# mega2560_EasyEDA_file.net
KiCad netlist of a schematic drawn in EasyEDA
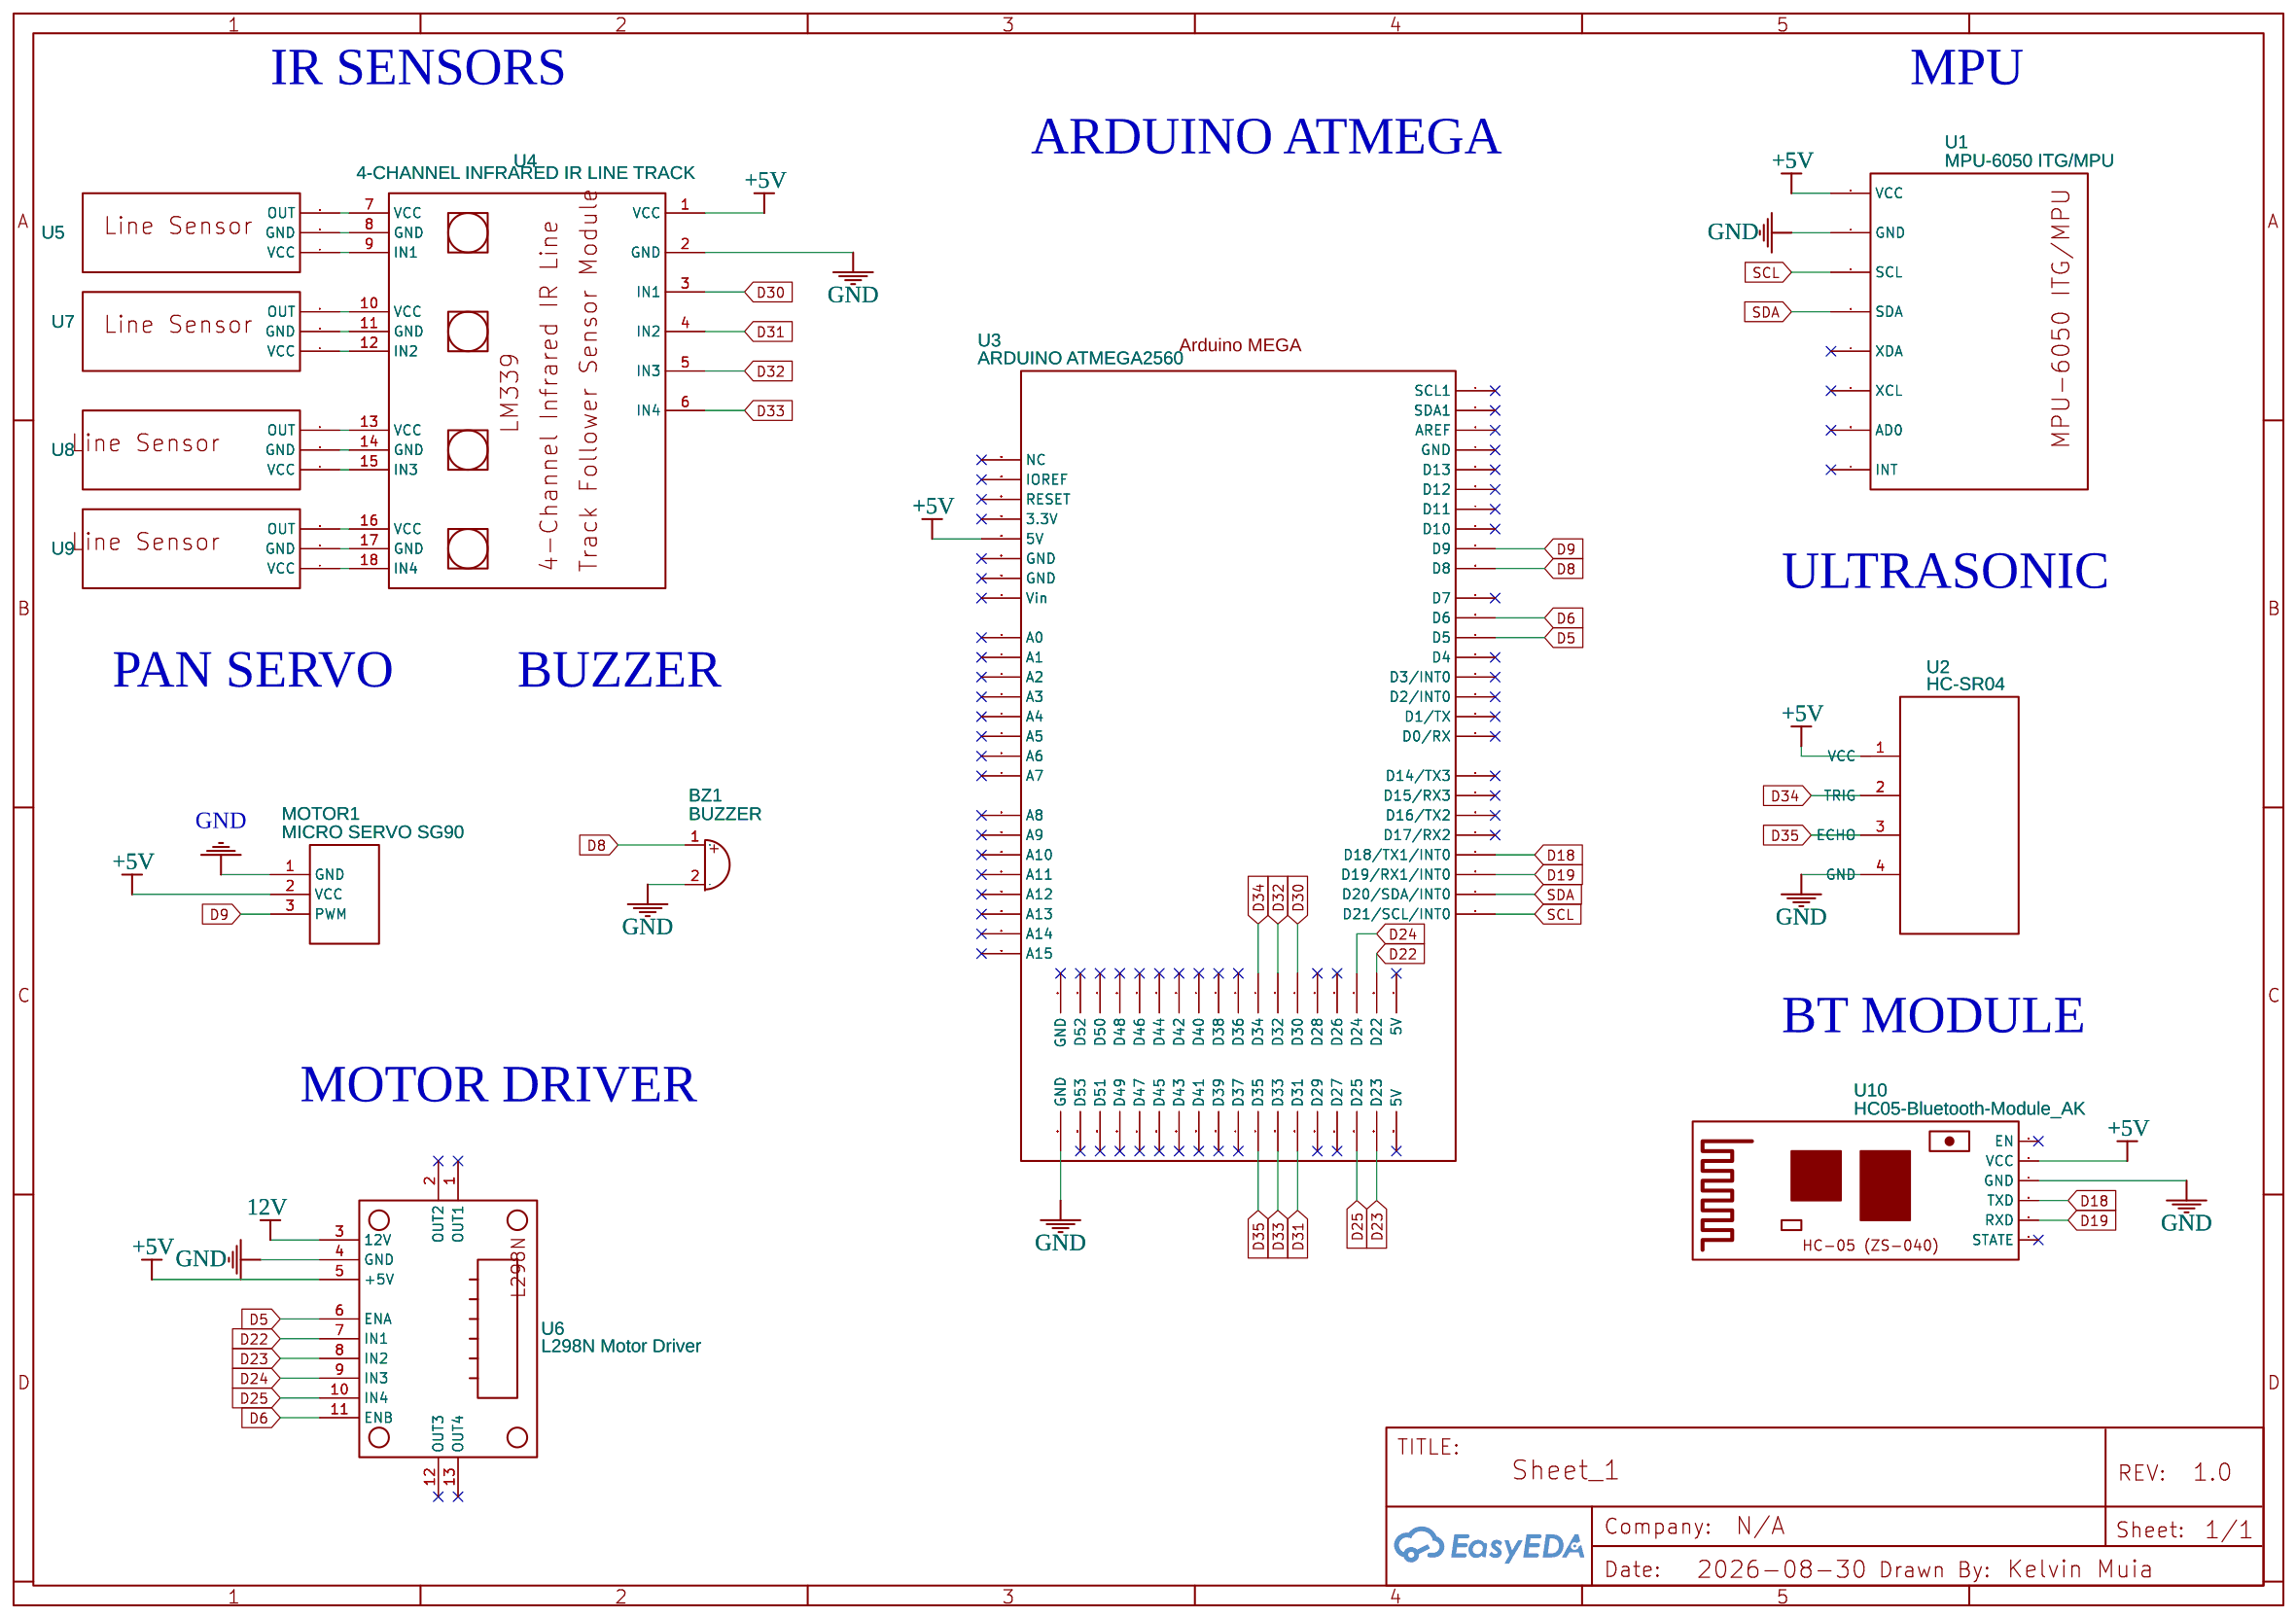
[diagram p0: schematic sheet]

(export (version "E")
  (design (tool "Eeschema 10.0.6"))
  (components
    (comp (ref "BZ1") (value "BUZZER") (libsource (lib "") (part "Device_Buzzer")))
    (comp (ref "MOTOR1") (value "MICRO SERVO SG90") (libsource (lib "") (part "MICRO SERVO SG90")))
    (comp (ref "U1") (value "MPU-6050 ITG/MPU") (libsource (lib "") (part "MPU-6050 ITG/MPU")))
    (comp (ref "U2") (value "HC-SR04") (libsource (lib "") (part "HC-SR04")))
    (comp (ref "U3") (value "ARDUINO ATMEGA2560") (libsource (lib "") (part "ARDUINO ATMEGA2560")))
    (comp (ref "U4")
      (value "4-CHANNEL INFRARED IR LINE TRACK")
      (fields (field (name "Manufacturer Part") "LM339"))
      (libsource (lib "") (part "4-CHANNEL INFRARED IR LINE TRACK FOLLOWER SENSOR MODULE (LM339) COPY"))
    )
    (comp (ref "U5")
      (value "MH-Sensor-Series Line Sensor")
      (libsource (lib "") (part "MH-Sensor-Series Line Sensor_1"))
    )
    (comp (ref "U6") (value "L298N Motor Driver") (libsource (lib "") (part "L298N Motor Driver")))
    (comp (ref "U7")
      (value "MH-Sensor-Series Line Sensor")
      (libsource (lib "") (part "MH-Sensor-Series Line Sensor_1"))
    )
    (comp (ref "U8")
      (value "MH-Sensor-Series Line Sensor")
      (libsource (lib "") (part "MH-Sensor-Series Line Sensor"))
    )
    (comp (ref "U9")
      (value "MH-Sensor-Series Line Sensor")
      (libsource (lib "") (part "MH-Sensor-Series Line Sensor"))
    )
    (comp (ref "U10")
      (value "HC05-Bluetooth-Module_AK")
      (libsource (lib "") (part "HC05-Bluetooth-Module_AK"))
    )
  )
  (nets
    (net (code "1") (name "+5V") (class "Default")
      (node (ref "MOTOR1") (pin "2") (pinfunction "VCC_2") (pintype "unspecified"))
      (node (ref "U1") (pin "0") (pinfunction "VCC_0") (pintype "unspecified"))
      (node (ref "U10") (pin "5") (pinfunction "VCC_5") (pintype "output"))
      (node (ref "U3") (pin "82") (pinfunction "5V_82") (pintype "unspecified"))
      (node (ref "U4") (pin "1") (pinfunction "VCC_1") (pintype "unspecified"))
      (node (ref "U6") (pin "5") (pinfunction "+5V_5") (pintype "unspecified"))
    )
    (net (code "2") (name "12V") (class "Default")
      (node (ref "U6") (pin "3") (pinfunction "12V_3") (pintype "unspecified"))
    )
    (net (code "3") (name "D5") (class "Default")
      (node (ref "U3") (pin "13") (pinfunction "D5_13") (pintype "unspecified"))
      (node (ref "U6") (pin "6") (pinfunction "ENA_6") (pintype "unspecified"))
    )
    (net (code "4") (name "D6") (class "Default")
      (node (ref "U3") (pin "12") (pinfunction "D6_12") (pintype "unspecified"))
      (node (ref "U6") (pin "11") (pinfunction "ENB_11") (pintype "unspecified"))
    )
    (net (code "5") (name "D8") (class "Default")
      (node (ref "BZ1") (pin "1") (pinfunction "+_1") (pintype "unspecified"))
      (node (ref "U3") (pin "10") (pinfunction "D8_10") (pintype "unspecified"))
    )
    (net (code "6") (name "D9") (class "Default")
      (node (ref "MOTOR1") (pin "3") (pinfunction "PWM_3") (pintype "unspecified"))
      (node (ref "U3") (pin "9") (pinfunction "D9_9") (pintype "unspecified"))
    )
    (net (code "7") (name "D18") (class "Default")
      (node (ref "U10") (pin "3") (pinfunction "TXD_3") (pintype "passive"))
      (node (ref "U3") (pin "23") (pinfunction "D18/TX1/INT0_23") (pintype "unspecified"))
    )
    (net (code "8") (name "D19") (class "Default")
      (node (ref "U10") (pin "2") (pinfunction "RXD_2") (pintype "passive"))
      (node (ref "U3") (pin "24") (pinfunction "D19/RX1/INT0_24") (pintype "unspecified"))
    )
    (net (code "9") (name "D22") (class "Default")
      (node (ref "U3") (pin "29") (pinfunction "D22_29") (pintype "unspecified"))
      (node (ref "U6") (pin "7") (pinfunction "IN1_7") (pintype "unspecified"))
    )
    (net (code "10") (name "D23") (class "Default")
      (node (ref "U3") (pin "30") (pinfunction "D23_30") (pintype "unspecified"))
      (node (ref "U6") (pin "8") (pinfunction "IN2_8") (pintype "unspecified"))
    )
    (net (code "11") (name "D24") (class "Default")
      (node (ref "U3") (pin "31") (pinfunction "D24_31") (pintype "unspecified"))
      (node (ref "U6") (pin "9") (pinfunction "IN3_9") (pintype "unspecified"))
    )
    (net (code "12") (name "D25") (class "Default")
      (node (ref "U3") (pin "32") (pinfunction "D25_32") (pintype "unspecified"))
      (node (ref "U6") (pin "10") (pinfunction "IN4_10") (pintype "unspecified"))
    )
    (net (code "13") (name "D30") (class "Default")
      (node (ref "U3") (pin "37") (pinfunction "D30_37") (pintype "unspecified"))
      (node (ref "U4") (pin "3") (pinfunction "IN1_3") (pintype "unspecified"))
    )
    (net (code "14") (name "D31") (class "Default")
      (node (ref "U3") (pin "38") (pinfunction "D31_38") (pintype "unspecified"))
      (node (ref "U4") (pin "4") (pinfunction "IN2_4") (pintype "unspecified"))
    )
    (net (code "15") (name "D32") (class "Default")
      (node (ref "U3") (pin "39") (pinfunction "D32_39") (pintype "unspecified"))
      (node (ref "U4") (pin "5") (pinfunction "IN3_5") (pintype "unspecified"))
    )
    (net (code "16") (name "D33") (class "Default")
      (node (ref "U3") (pin "40") (pinfunction "D33_40") (pintype "unspecified"))
      (node (ref "U4") (pin "6") (pinfunction "IN4_6") (pintype "unspecified"))
    )
    (net (code "17") (name "D34") (class "Default")
      (node (ref "U3") (pin "41") (pinfunction "D34_41") (pintype "unspecified"))
    )
    (net (code "18") (name "D35") (class "Default")
      (node (ref "U3") (pin "42") (pinfunction "D35_42") (pintype "unspecified"))
    )
    (net (code "19") (name "GND") (class "Default")
      (node (ref "BZ1") (pin "2") (pinfunction "-_2") (pintype "unspecified"))
      (node (ref "MOTOR1") (pin "1") (pinfunction "GND_1") (pintype "unspecified"))
      (node (ref "U1") (pin "1") (pinfunction "GND_1") (pintype "unspecified"))
      (node (ref "U10") (pin "4") (pinfunction "GND_4") (pintype "input"))
      (node (ref "U3") (pin "62") (pinfunction "GND_62") (pintype "unspecified"))
      (node (ref "U4") (pin "2") (pinfunction "GND_2") (pintype "unspecified"))
      (node (ref "U6") (pin "4") (pinfunction "GND_4") (pintype "unspecified"))
    )
    (net (code "20") (name "Net-(U5-GND)") (class "Default")
      (node (ref "U4") (pin "8") (pinfunction "GND_8") (pintype "unspecified"))
      (node (ref "U5") (pin "3") (pinfunction "GND_3") (pintype "passive"))
    )
    (net (code "21") (name "Net-(U5-OUT)") (class "Default")
      (node (ref "U4") (pin "7") (pinfunction "VCC_7") (pintype "unspecified"))
      (node (ref "U5") (pin "2") (pinfunction "OUT_2") (pintype "unspecified"))
    )
    (net (code "22") (name "Net-(U5-VCC)") (class "Default")
      (node (ref "U4") (pin "9") (pinfunction "IN1_9") (pintype "unspecified"))
      (node (ref "U5") (pin "4") (pinfunction "VCC_4") (pintype "passive"))
    )
    (net (code "23") (name "Net-(U7-GND)") (class "Default")
      (node (ref "U4") (pin "11") (pinfunction "GND_11") (pintype "unspecified"))
      (node (ref "U7") (pin "3") (pinfunction "GND_3") (pintype "passive"))
    )
    (net (code "24") (name "Net-(U7-OUT)") (class "Default")
      (node (ref "U4") (pin "10") (pinfunction "VCC_10") (pintype "unspecified"))
      (node (ref "U7") (pin "2") (pinfunction "OUT_2") (pintype "unspecified"))
    )
    (net (code "25") (name "Net-(U7-VCC)") (class "Default")
      (node (ref "U4") (pin "12") (pinfunction "IN2_12") (pintype "unspecified"))
      (node (ref "U7") (pin "4") (pinfunction "VCC_4") (pintype "passive"))
    )
    (net (code "26") (name "Net-(U8-GND)") (class "Default")
      (node (ref "U4") (pin "14") (pinfunction "GND_14") (pintype "unspecified"))
      (node (ref "U8") (pin "3") (pinfunction "GND_3") (pintype "passive"))
    )
    (net (code "27") (name "Net-(U8-OUT)") (class "Default")
      (node (ref "U4") (pin "13") (pinfunction "VCC_13") (pintype "unspecified"))
      (node (ref "U8") (pin "2") (pinfunction "OUT_2") (pintype "unspecified"))
    )
    (net (code "28") (name "Net-(U8-VCC)") (class "Default")
      (node (ref "U4") (pin "15") (pinfunction "IN3_15") (pintype "unspecified"))
      (node (ref "U8") (pin "4") (pinfunction "VCC_4") (pintype "passive"))
    )
    (net (code "29") (name "Net-(U9-GND)") (class "Default")
      (node (ref "U4") (pin "17") (pinfunction "GND_17") (pintype "unspecified"))
      (node (ref "U9") (pin "3") (pinfunction "GND_3") (pintype "passive"))
    )
    (net (code "30") (name "Net-(U9-OUT)") (class "Default")
      (node (ref "U4") (pin "16") (pinfunction "VCC_16") (pintype "unspecified"))
      (node (ref "U9") (pin "2") (pinfunction "OUT_2") (pintype "unspecified"))
    )
    (net (code "31") (name "Net-(U9-VCC)") (class "Default")
      (node (ref "U4") (pin "18") (pinfunction "IN4_18") (pintype "unspecified"))
      (node (ref "U9") (pin "4") (pinfunction "VCC_4") (pintype "passive"))
    )
    (net (code "32") (name "SCL") (class "Default")
      (node (ref "U1") (pin "2") (pinfunction "SCL_2") (pintype "unspecified"))
      (node (ref "U3") (pin "26") (pinfunction "D21/SCL/INT0_26") (pintype "unspecified"))
    )
    (net (code "33") (name "SDA") (class "Default")
      (node (ref "U1") (pin "3") (pinfunction "SDA_3") (pintype "unspecified"))
      (node (ref "U3") (pin "25") (pinfunction "D20/SDA/INT0_25") (pintype "unspecified"))
    )
    (net (code "34") (name "unconnected-(U1-AD0-Pad6)") (class "Default")
      (node (ref "U1") (pin "6") (pinfunction "AD0_6") (pintype "unspecified+no_connect"))
    )
    (net (code "35") (name "unconnected-(U1-INT-Pad7)") (class "Default")
      (node (ref "U1") (pin "7") (pinfunction "INT_7") (pintype "unspecified+no_connect"))
    )
    (net (code "36") (name "unconnected-(U1-XCL-Pad5)") (class "Default")
      (node (ref "U1") (pin "5") (pinfunction "XCL_5") (pintype "unspecified+no_connect"))
    )
    (net (code "37") (name "unconnected-(U1-XDA-Pad4)") (class "Default")
      (node (ref "U1") (pin "4") (pinfunction "XDA_4") (pintype "unspecified+no_connect"))
    )
    (net (code "38") (name "unconnected-(U2-ECHO-Pad3)") (class "Default")
      (node (ref "U2") (pin "3") (pinfunction "ECHO_3") (pintype "unspecified"))
    )
    (net (code "39") (name "unconnected-(U2-GND-Pad4)") (class "Default")
      (node (ref "U2") (pin "4") (pinfunction "GND_4") (pintype "unspecified"))
    )
    (net (code "40") (name "unconnected-(U2-TRIG-Pad2)") (class "Default")
      (node (ref "U2") (pin "2") (pinfunction "TRIG_2") (pintype "unspecified"))
    )
    (net (code "41") (name "unconnected-(U2-VCC-Pad1)") (class "Default")
      (node (ref "U2") (pin "1") (pinfunction "VCC_1") (pintype "unspecified"))
    )
    (net (code "42") (name "unconnected-(U3-3.3V-Pad83)") (class "Default")
      (node (ref "U3") (pin "83") (pinfunction "3.3V_83") (pintype "unspecified+no_connect"))
    )
    (net (code "43") (name "unconnected-(U3-5V-Pad27)") (class "Default")
      (node (ref "U3") (pin "27") (pinfunction "5V_27") (pintype "unspecified+no_connect"))
    )
    (net (code "44") (name "unconnected-(U3-5V-Pad28)") (class "Default")
      (node (ref "U3") (pin "28") (pinfunction "5V_28") (pintype "unspecified+no_connect"))
    )
    (net (code "45") (name "unconnected-(U3-A0-Pad78)") (class "Default")
      (node (ref "U3") (pin "78") (pinfunction "A0_78") (pintype "unspecified+no_connect"))
    )
    (net (code "46") (name "unconnected-(U3-A1-Pad77)") (class "Default")
      (node (ref "U3") (pin "77") (pinfunction "A1_77") (pintype "unspecified+no_connect"))
    )
    (net (code "47") (name "unconnected-(U3-A2-Pad76)") (class "Default")
      (node (ref "U3") (pin "76") (pinfunction "A2_76") (pintype "unspecified+no_connect"))
    )
    (net (code "48") (name "unconnected-(U3-A3-Pad75)") (class "Default")
      (node (ref "U3") (pin "75") (pinfunction "A3_75") (pintype "unspecified+no_connect"))
    )
    (net (code "49") (name "unconnected-(U3-A4-Pad74)") (class "Default")
      (node (ref "U3") (pin "74") (pinfunction "A4_74") (pintype "unspecified+no_connect"))
    )
    (net (code "50") (name "unconnected-(U3-A5-Pad73)") (class "Default")
      (node (ref "U3") (pin "73") (pinfunction "A5_73") (pintype "unspecified+no_connect"))
    )
    (net (code "51") (name "unconnected-(U3-A6-Pad72)") (class "Default")
      (node (ref "U3") (pin "72") (pinfunction "A6_72") (pintype "unspecified+no_connect"))
    )
    (net (code "52") (name "unconnected-(U3-A7-Pad71)") (class "Default")
      (node (ref "U3") (pin "71") (pinfunction "A7_71") (pintype "unspecified+no_connect"))
    )
    (net (code "53") (name "unconnected-(U3-A8-Pad70)") (class "Default")
      (node (ref "U3") (pin "70") (pinfunction "A8_70") (pintype "unspecified+no_connect"))
    )
    (net (code "54") (name "unconnected-(U3-A9-Pad69)") (class "Default")
      (node (ref "U3") (pin "69") (pinfunction "A9_69") (pintype "unspecified+no_connect"))
    )
    (net (code "55") (name "unconnected-(U3-A10-Pad68)") (class "Default")
      (node (ref "U3") (pin "68") (pinfunction "A10_68") (pintype "unspecified+no_connect"))
    )
    (net (code "56") (name "unconnected-(U3-A11-Pad67)") (class "Default")
      (node (ref "U3") (pin "67") (pinfunction "A11_67") (pintype "unspecified+no_connect"))
    )
    (net (code "57") (name "unconnected-(U3-A12-Pad66)") (class "Default")
      (node (ref "U3") (pin "66") (pinfunction "A12_66") (pintype "unspecified+no_connect"))
    )
    (net (code "58") (name "unconnected-(U3-A13-Pad65)") (class "Default")
      (node (ref "U3") (pin "65") (pinfunction "A13_65") (pintype "unspecified+no_connect"))
    )
    (net (code "59") (name "unconnected-(U3-A14-Pad64)") (class "Default")
      (node (ref "U3") (pin "64") (pinfunction "A14_64") (pintype "unspecified+no_connect"))
    )
    (net (code "60") (name "unconnected-(U3-A15-Pad63)") (class "Default")
      (node (ref "U3") (pin "63") (pinfunction "A15_63") (pintype "unspecified+no_connect"))
    )
    (net (code "61") (name "unconnected-(U3-AREF-Pad3)") (class "Default")
      (node (ref "U3") (pin "3") (pinfunction "AREF_3") (pintype "unspecified+no_connect"))
    )
    (net (code "62") (name "unconnected-(U3-D0{slash}RX-Pad18)") (class "Default")
      (node (ref "U3") (pin "18") (pinfunction "D0/RX_18") (pintype "unspecified+no_connect"))
    )
    (net (code "63") (name "unconnected-(U3-D1{slash}TX-Pad17)") (class "Default")
      (node (ref "U3") (pin "17") (pinfunction "D1/TX_17") (pintype "unspecified+no_connect"))
    )
    (net (code "64") (name "unconnected-(U3-D2{slash}INT0-Pad16)") (class "Default")
      (node (ref "U3") (pin "16") (pinfunction "D2/INT0_16") (pintype "unspecified+no_connect"))
    )
    (net (code "65") (name "unconnected-(U3-D3{slash}INT0-Pad15)") (class "Default")
      (node (ref "U3") (pin "15") (pinfunction "D3/INT0_15") (pintype "unspecified+no_connect"))
    )
    (net (code "66") (name "unconnected-(U3-D4-Pad14)") (class "Default")
      (node (ref "U3") (pin "14") (pinfunction "D4_14") (pintype "unspecified+no_connect"))
    )
    (net (code "67") (name "unconnected-(U3-D7-Pad11)") (class "Default")
      (node (ref "U3") (pin "11") (pinfunction "D7_11") (pintype "unspecified+no_connect"))
    )
    (net (code "68") (name "unconnected-(U3-D10-Pad8)") (class "Default")
      (node (ref "U3") (pin "8") (pinfunction "D10_8") (pintype "unspecified+no_connect"))
    )
    (net (code "69") (name "unconnected-(U3-D11-Pad7)") (class "Default")
      (node (ref "U3") (pin "7") (pinfunction "D11_7") (pintype "unspecified+no_connect"))
    )
    (net (code "70") (name "unconnected-(U3-D12-Pad6)") (class "Default")
      (node (ref "U3") (pin "6") (pinfunction "D12_6") (pintype "unspecified+no_connect"))
    )
    (net (code "71") (name "unconnected-(U3-D13-Pad5)") (class "Default")
      (node (ref "U3") (pin "5") (pinfunction "D13_5") (pintype "unspecified+no_connect"))
    )
    (net (code "72") (name "unconnected-(U3-D14{slash}TX3-Pad19)") (class "Default")
      (node (ref "U3") (pin "19") (pinfunction "D14/TX3_19") (pintype "unspecified+no_connect"))
    )
    (net (code "73") (name "unconnected-(U3-D15{slash}RX3-Pad20)") (class "Default")
      (node (ref "U3") (pin "20") (pinfunction "D15/RX3_20") (pintype "unspecified+no_connect"))
    )
    (net (code "74") (name "unconnected-(U3-D16{slash}TX2-Pad21)") (class "Default")
      (node (ref "U3") (pin "21") (pinfunction "D16/TX2_21") (pintype "unspecified+no_connect"))
    )
    (net (code "75") (name "unconnected-(U3-D17{slash}RX2-Pad22)") (class "Default")
      (node (ref "U3") (pin "22") (pinfunction "D17/RX2_22") (pintype "unspecified+no_connect"))
    )
    (net (code "76") (name "unconnected-(U3-D26-Pad33)") (class "Default")
      (node (ref "U3") (pin "33") (pinfunction "D26_33") (pintype "unspecified+no_connect"))
    )
    (net (code "77") (name "unconnected-(U3-D27-Pad34)") (class "Default")
      (node (ref "U3") (pin "34") (pinfunction "D27_34") (pintype "unspecified+no_connect"))
    )
    (net (code "78") (name "unconnected-(U3-D28-Pad35)") (class "Default")
      (node (ref "U3") (pin "35") (pinfunction "D28_35") (pintype "unspecified+no_connect"))
    )
    (net (code "79") (name "unconnected-(U3-D29-Pad36)") (class "Default")
      (node (ref "U3") (pin "36") (pinfunction "D29_36") (pintype "unspecified+no_connect"))
    )
    (net (code "80") (name "unconnected-(U3-D36-Pad43)") (class "Default")
      (node (ref "U3") (pin "43") (pinfunction "D36_43") (pintype "unspecified+no_connect"))
    )
    (net (code "81") (name "unconnected-(U3-D37-Pad44)") (class "Default")
      (node (ref "U3") (pin "44") (pinfunction "D37_44") (pintype "unspecified+no_connect"))
    )
    (net (code "82") (name "unconnected-(U3-D38-Pad45)") (class "Default")
      (node (ref "U3") (pin "45") (pinfunction "D38_45") (pintype "unspecified+no_connect"))
    )
    (net (code "83") (name "unconnected-(U3-D39-Pad46)") (class "Default")
      (node (ref "U3") (pin "46") (pinfunction "D39_46") (pintype "unspecified+no_connect"))
    )
    (net (code "84") (name "unconnected-(U3-D40-Pad47)") (class "Default")
      (node (ref "U3") (pin "47") (pinfunction "D40_47") (pintype "unspecified+no_connect"))
    )
    (net (code "85") (name "unconnected-(U3-D41-Pad48)") (class "Default")
      (node (ref "U3") (pin "48") (pinfunction "D41_48") (pintype "unspecified+no_connect"))
    )
    (net (code "86") (name "unconnected-(U3-D42-Pad49)") (class "Default")
      (node (ref "U3") (pin "49") (pinfunction "D42_49") (pintype "unspecified+no_connect"))
    )
    (net (code "87") (name "unconnected-(U3-D43-Pad50)") (class "Default")
      (node (ref "U3") (pin "50") (pinfunction "D43_50") (pintype "unspecified+no_connect"))
    )
    (net (code "88") (name "unconnected-(U3-D44-Pad51)") (class "Default")
      (node (ref "U3") (pin "51") (pinfunction "D44_51") (pintype "unspecified+no_connect"))
    )
    (net (code "89") (name "unconnected-(U3-D45-Pad52)") (class "Default")
      (node (ref "U3") (pin "52") (pinfunction "D45_52") (pintype "unspecified+no_connect"))
    )
    (net (code "90") (name "unconnected-(U3-D46-Pad53)") (class "Default")
      (node (ref "U3") (pin "53") (pinfunction "D46_53") (pintype "unspecified+no_connect"))
    )
    (net (code "91") (name "unconnected-(U3-D47-Pad54)") (class "Default")
      (node (ref "U3") (pin "54") (pinfunction "D47_54") (pintype "unspecified+no_connect"))
    )
    (net (code "92") (name "unconnected-(U3-D48-Pad55)") (class "Default")
      (node (ref "U3") (pin "55") (pinfunction "D48_55") (pintype "unspecified+no_connect"))
    )
    (net (code "93") (name "unconnected-(U3-D49-Pad56)") (class "Default")
      (node (ref "U3") (pin "56") (pinfunction "D49_56") (pintype "unspecified+no_connect"))
    )
    (net (code "94") (name "unconnected-(U3-D50-Pad57)") (class "Default")
      (node (ref "U3") (pin "57") (pinfunction "D50_57") (pintype "unspecified+no_connect"))
    )
    (net (code "95") (name "unconnected-(U3-D51-Pad58)") (class "Default")
      (node (ref "U3") (pin "58") (pinfunction "D51_58") (pintype "unspecified+no_connect"))
    )
    (net (code "96") (name "unconnected-(U3-D52-Pad59)") (class "Default")
      (node (ref "U3") (pin "59") (pinfunction "D52_59") (pintype "unspecified+no_connect"))
    )
    (net (code "97") (name "unconnected-(U3-D53-Pad60)") (class "Default")
      (node (ref "U3") (pin "60") (pinfunction "D53_60") (pintype "unspecified+no_connect"))
    )
    (net (code "98") (name "unconnected-(U3-GND-Pad4)") (class "Default")
      (node (ref "U3") (pin "4") (pinfunction "GND_4") (pintype "unspecified+no_connect"))
    )
    (net (code "99") (name "unconnected-(U3-GND-Pad61)") (class "Default")
      (node (ref "U3") (pin "61") (pinfunction "GND_61") (pintype "unspecified+no_connect"))
    )
    (net (code "100") (name "unconnected-(U3-GND-Pad80)") (class "Default")
      (node (ref "U3") (pin "80") (pinfunction "GND_80") (pintype "unspecified+no_connect"))
    )
    (net (code "101") (name "unconnected-(U3-GND-Pad81)") (class "Default")
      (node (ref "U3") (pin "81") (pinfunction "GND_81") (pintype "unspecified+no_connect"))
    )
    (net (code "102") (name "unconnected-(U3-IOREF-Pad85)") (class "Default")
      (node (ref "U3") (pin "85") (pinfunction "IOREF_85") (pintype "unspecified+no_connect"))
    )
    (net (code "103") (name "unconnected-(U3-NC-Pad86)") (class "Default")
      (node (ref "U3") (pin "86") (pinfunction "NC_86") (pintype "unspecified+no_connect"))
    )
    (net (code "104") (name "unconnected-(U3-RESET-Pad84)") (class "Default")
      (node (ref "U3") (pin "84") (pinfunction "RESET_84") (pintype "unspecified+no_connect"))
    )
    (net (code "105") (name "unconnected-(U3-SCL1-Pad1)") (class "Default")
      (node (ref "U3") (pin "1") (pinfunction "SCL1_1") (pintype "unspecified+no_connect"))
    )
    (net (code "106") (name "unconnected-(U3-SDA1-Pad2)") (class "Default")
      (node (ref "U3") (pin "2") (pinfunction "SDA1_2") (pintype "unspecified+no_connect"))
    )
    (net (code "107") (name "unconnected-(U3-Vin-Pad79)") (class "Default")
      (node (ref "U3") (pin "79") (pinfunction "Vin_79") (pintype "unspecified+no_connect"))
    )
    (net (code "108") (name "unconnected-(U6-OUT1-Pad1)") (class "Default")
      (node (ref "U6") (pin "1") (pinfunction "OUT1_1") (pintype "unspecified+no_connect"))
    )
    (net (code "109") (name "unconnected-(U6-OUT2-Pad2)") (class "Default")
      (node (ref "U6") (pin "2") (pinfunction "OUT2_2") (pintype "unspecified+no_connect"))
    )
    (net (code "110") (name "unconnected-(U6-OUT3-Pad12)") (class "Default")
      (node (ref "U6") (pin "12") (pinfunction "OUT3_12") (pintype "unspecified+no_connect"))
    )
    (net (code "111") (name "unconnected-(U6-OUT4-Pad13)") (class "Default")
      (node (ref "U6") (pin "13") (pinfunction "OUT4_13") (pintype "unspecified+no_connect"))
    )
    (net (code "112") (name "unconnected-(U10-EN-Pad6)") (class "Default")
      (node (ref "U10") (pin "6") (pinfunction "EN_6") (pintype "bidirectional+no_connect"))
    )
    (net (code "113") (name "unconnected-(U10-STATE-Pad1)") (class "Default")
      (node (ref "U10") (pin "1") (pinfunction "STATE_1") (pintype "passive+no_connect"))
    )
  )
)
